# quadcopter_2.net
KiCad netlist of a schematic drawn in EAGLE
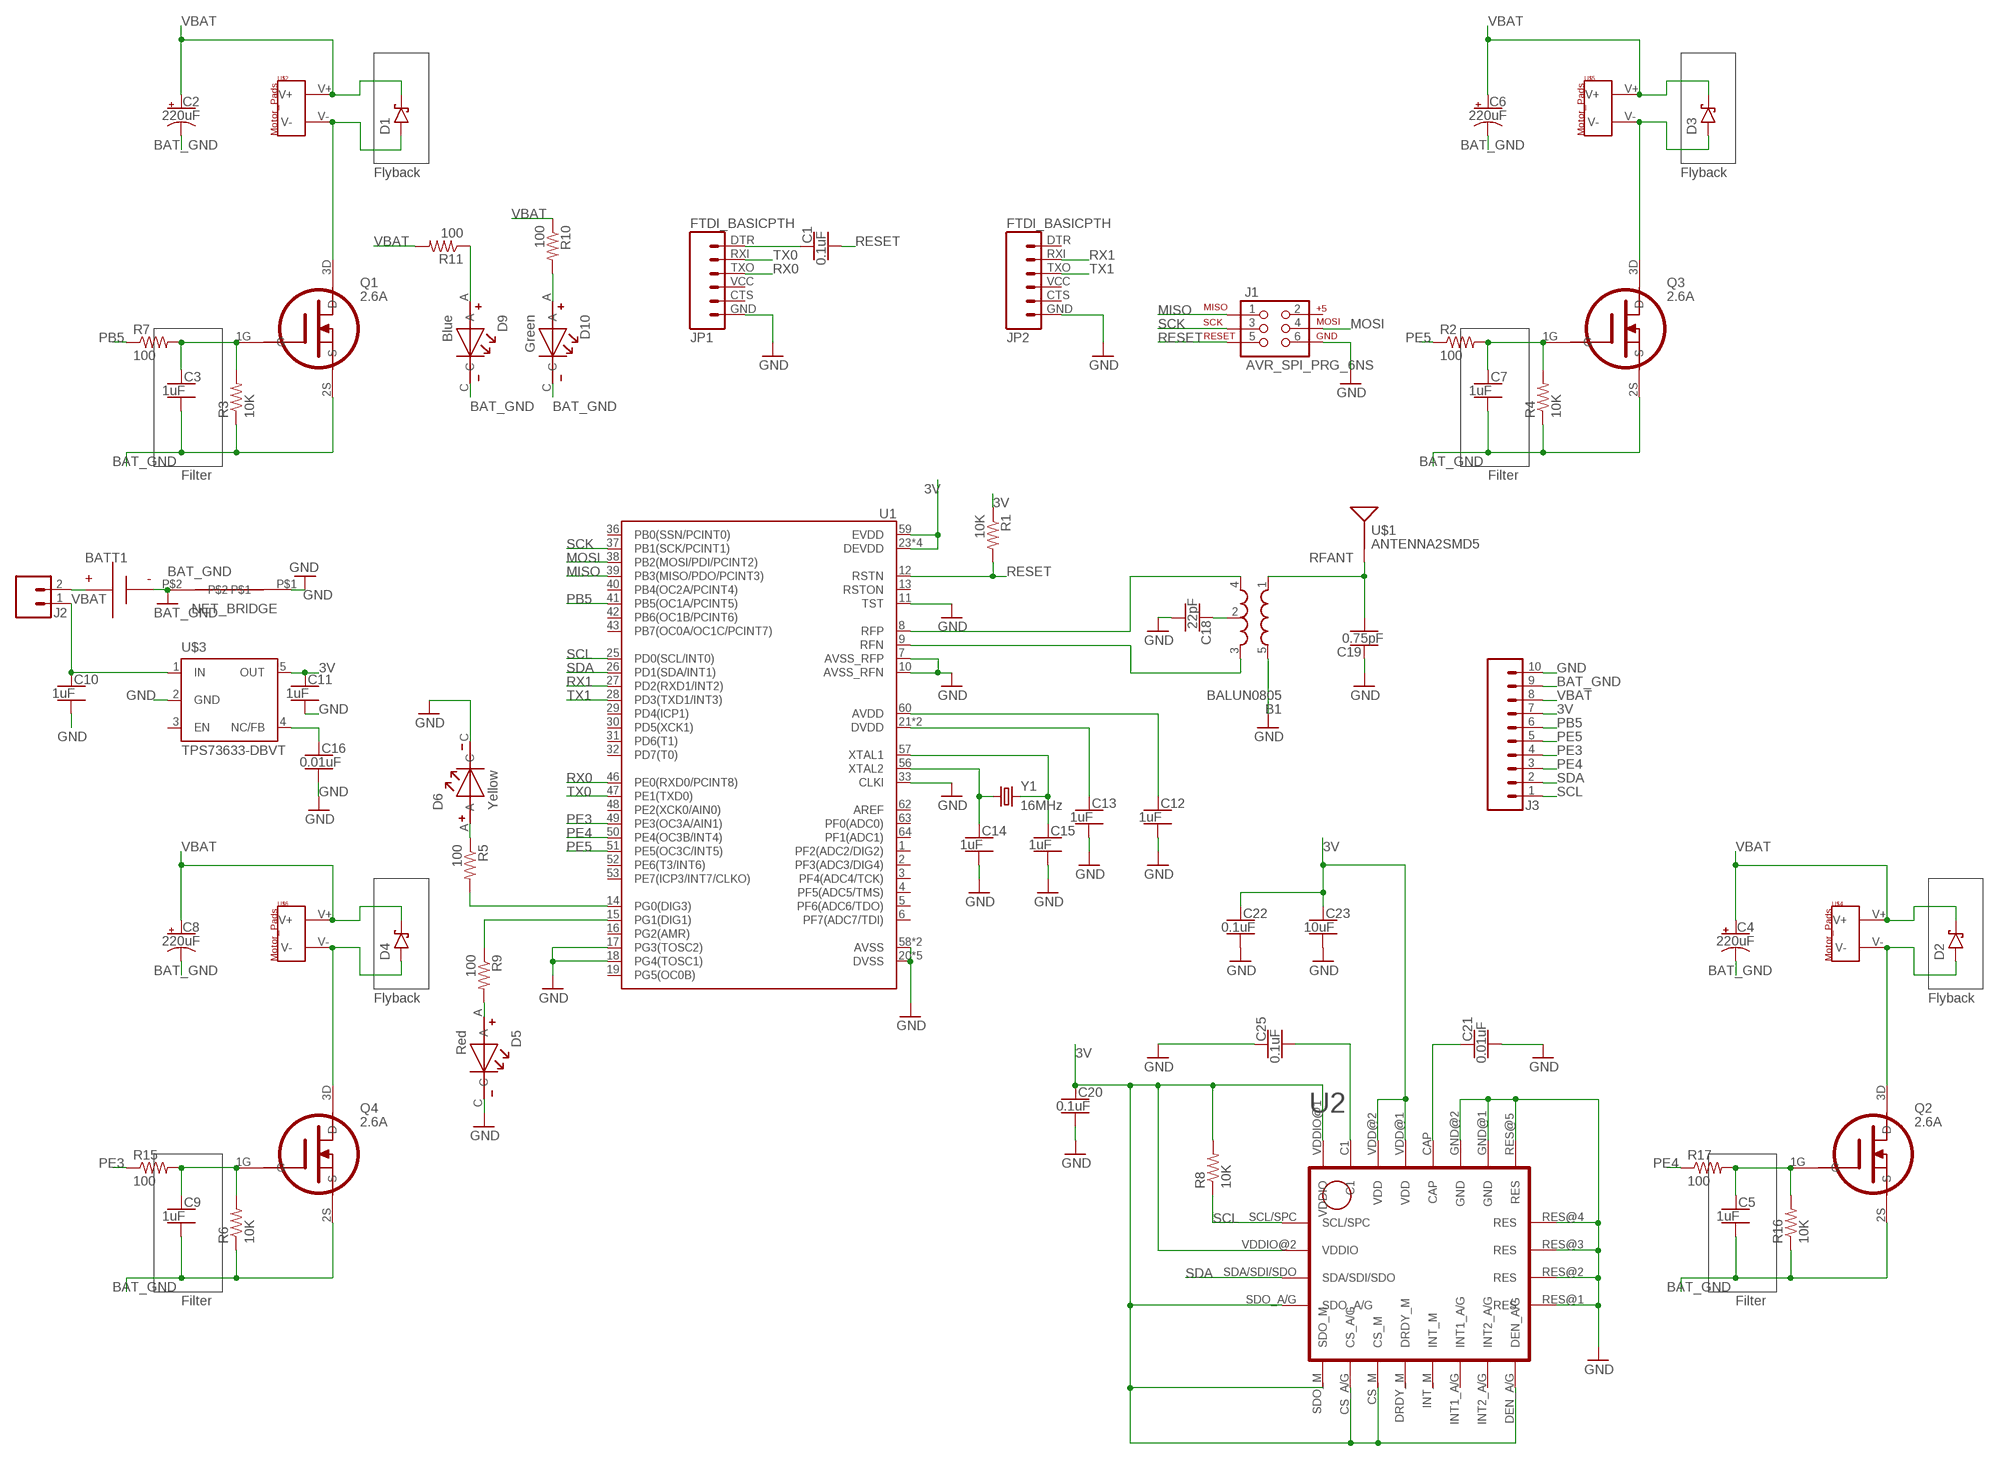
[diagram p0: schematic, sheet 1]

(export (version "E")
  (design (tool "Eeschema 10.0.6"))
  (components
    (comp (ref "B1")
      (value "BALUN0805")
      (footprint "eagle-import:BALUN")
      (fields (field (name "MFR") "Wurth Electronics Inc") (field (name "MPN") "748421245"))
      (libsource (lib "eagle-import") (part "BALUN0805"))
    )
    (comp (ref "BATT1")
      (value "BATTERY-HUBSAN-W/HOLDER")
      (footprint "eagle-import:BATTERY-W_HOLDER-380MAH-HUBSAN")
      (fields
        (field (name "MFR") "HUBSAN")
        (field (name "MPN") "X4-H107C-8-in-1")
        (field (name "CREATOR") "Swanson")
      )
      (libsource (lib "eagle-import") (part "BATTERY-HUBSAN-W/HOLDER"))
    )
    (comp (ref "C1")
      (value "0.1uF")
      (footprint "eagle-import:CERAMIC_CAP_0805")
      (fields
        (field (name "MFR") "Murata Electronics North America")
        (field (name "MPN") "GRM21BR71H104KA01L")
        (field (name "CREATOR") "SWANSON")
      )
      (libsource (lib "eagle-import") (part "CERAMIC_CAP-0805-0.1UF"))
    )
    (comp (ref "C2")
      (value "220uF")
      (footprint "eagle-import:CAPMP7343X310_HS")
      (fields (field (name "MFR") "AVX Corporation") (field (name "MPN") "TAJD227K006RNJ"))
      (libsource (lib "eagle-import") (part "CAPACITOR-POL_SMD-7043-D_TANTALUM-220UF"))
    )
    (comp (ref "C3")
      (value "1uF")
      (footprint "eagle-import:CAPC2012X140_HS")
      (fields
        (field (name "MFR") "Murata Electronics North America")
        (field (name "MPN") "GRM21BR71H105KA12L")
      )
      (libsource (lib "eagle-import") (part "CAPACITOR-NP_SMD-2012-0805_CERAMIC-1UF"))
    )
    (comp (ref "C4")
      (value "220uF")
      (footprint "eagle-import:CAPMP7343X310_HS")
      (fields (field (name "MFR") "AVX Corporation") (field (name "MPN") "TAJD227K006RNJ"))
      (libsource (lib "eagle-import") (part "CAPACITOR-POL_SMD-7043-D_TANTALUM-220UF"))
    )
    (comp (ref "C5")
      (value "1uF")
      (footprint "eagle-import:CAPC2012X140_HS")
      (fields
        (field (name "MFR") "Murata Electronics North America")
        (field (name "MPN") "GRM21BR71H105KA12L")
      )
      (libsource (lib "eagle-import") (part "CAPACITOR-NP_SMD-2012-0805_CERAMIC-1UF"))
    )
    (comp (ref "C6")
      (value "220uF")
      (footprint "eagle-import:CAPMP7343X310_HS")
      (fields (field (name "MFR") "AVX Corporation") (field (name "MPN") "TAJD227K006RNJ"))
      (libsource (lib "eagle-import") (part "CAPACITOR-POL_SMD-7043-D_TANTALUM-220UF"))
    )
    (comp (ref "C7")
      (value "1uF")
      (footprint "eagle-import:CAPC2012X140_HS")
      (fields
        (field (name "MFR") "Murata Electronics North America")
        (field (name "MPN") "GRM21BR71H105KA12L")
      )
      (libsource (lib "eagle-import") (part "CAPACITOR-NP_SMD-2012-0805_CERAMIC-1UF"))
    )
    (comp (ref "C8")
      (value "220uF")
      (footprint "eagle-import:CAPMP7343X310_HS")
      (fields (field (name "MFR") "AVX Corporation") (field (name "MPN") "TAJD227K006RNJ"))
      (libsource (lib "eagle-import") (part "CAPACITOR-POL_SMD-7043-D_TANTALUM-220UF"))
    )
    (comp (ref "C9")
      (value "1uF")
      (footprint "eagle-import:CAPC2012X140_HS")
      (fields
        (field (name "MFR") "Murata Electronics North America")
        (field (name "MPN") "GRM21BR71H105KA12L")
      )
      (libsource (lib "eagle-import") (part "CAPACITOR-NP_SMD-2012-0805_CERAMIC-1UF"))
    )
    (comp (ref "C10")
      (value "1uF")
      (footprint "eagle-import:CAPC2012X140_HS")
      (fields
        (field (name "MFR") "Murata Electronics North America")
        (field (name "MPN") "GRM21BR71H105KA12L")
      )
      (libsource (lib "eagle-import") (part "CAPACITOR-NP_SMD-2012-0805_CERAMIC-1UF"))
    )
    (comp (ref "C11")
      (value "1uF")
      (footprint "eagle-import:CAPC2012X140_HS")
      (fields
        (field (name "MFR") "Murata Electronics North America")
        (field (name "MPN") "GRM21BR71H105KA12L")
      )
      (libsource (lib "eagle-import") (part "CAPACITOR-NP_SMD-2012-0805_CERAMIC-1UF"))
    )
    (comp (ref "C12")
      (value "1uF")
      (footprint "eagle-import:CAPC2012X140_HS")
      (fields
        (field (name "MFR") "Murata Electronics North America")
        (field (name "MPN") "GRM21BR71H105KA12L")
      )
      (libsource (lib "eagle-import") (part "CAPACITOR-NP_SMD-2012-0805_CERAMIC-1UF"))
    )
    (comp (ref "C13")
      (value "1uF")
      (footprint "eagle-import:CAPC2012X140_HS")
      (fields
        (field (name "MFR") "Murata Electronics North America")
        (field (name "MPN") "GRM21BR71H105KA12L")
      )
      (libsource (lib "eagle-import") (part "CAPACITOR-NP_SMD-2012-0805_CERAMIC-1UF"))
    )
    (comp (ref "C14")
      (value "1uF")
      (footprint "eagle-import:CAPC2012X140_HS")
      (fields
        (field (name "MFR") "Murata Electronics North America")
        (field (name "MPN") "GRM21BR71H105KA12L")
      )
      (libsource (lib "eagle-import") (part "CAPACITOR-NP_SMD-2012-0805_CERAMIC-1UF"))
    )
    (comp (ref "C15")
      (value "1uF")
      (footprint "eagle-import:CAPC2012X140_HS")
      (fields
        (field (name "MFR") "Murata Electronics North America")
        (field (name "MPN") "GRM21BR71H105KA12L")
      )
      (libsource (lib "eagle-import") (part "CAPACITOR-NP_SMD-2012-0805_CERAMIC-1UF"))
    )
    (comp (ref "C16")
      (value "0.01uF")
      (footprint "eagle-import:CAPC2012X140_HS")
      (fields
        (field (name "MFR") "Murata Electronics North America")
        (field (name "MPN") "GRM2195C1H103FA01D")
      )
      (libsource (lib "eagle-import") (part "CAPACITOR-NP_SMD-2012-0805_CERAMIC-0.01UF"))
    )
    (comp (ref "C18")
      (value "22pF")
      (footprint "eagle-import:CAPC2012X140_HS")
      (fields
        (field (name "MFR") "Murata Electronics North America")
        (field (name "MPN") "GRM21A5C2E220JW01D")
      )
      (libsource (lib "eagle-import") (part "CAPACITOR-NP_SMD-2012-0805_CERAMIC-22PF"))
    )
    (comp (ref "C19")
      (value "0.75pF")
      (footprint "eagle-import:CAPC2012X140_HS")
      (fields
        (field (name "MFR") "Murata Electronics North America")
        (field (name "MPN") "GQM2195C2AR75CB01D")
      )
      (libsource (lib "eagle-import") (part "CAPACITOR-NP_SMD-2012-0805_CERAMIC-0.75PF"))
    )
    (comp (ref "C20")
      (value "0.1uF")
      (footprint "eagle-import:CAPC2012X140_HS")
      (fields
        (field (name "MFR") "Murata Electronics North America")
        (field (name "MPN") "GRM21BR71H104KA01L")
      )
      (libsource (lib "eagle-import") (part "CAPACITOR-NP_SMD-2012-0805_CERAMIC-0.1UF"))
    )
    (comp (ref "C21")
      (value "0.01uF")
      (footprint "eagle-import:CAPC2012X140_HS")
      (fields
        (field (name "MFR") "Murata Electronics North America")
        (field (name "MPN") "GRM2195C1H103FA01D")
      )
      (libsource (lib "eagle-import") (part "CAPACITOR-NP_SMD-2012-0805_CERAMIC-0.01UF"))
    )
    (comp (ref "C22")
      (value "0.1uF")
      (footprint "eagle-import:CAPC2012X140_HS")
      (fields
        (field (name "MFR") "Murata Electronics North America")
        (field (name "MPN") "GRM21BR71H104KA01L")
      )
      (libsource (lib "eagle-import") (part "CAPACITOR-NP_SMD-2012-0805_CERAMIC-0.1UF"))
    )
    (comp (ref "C23")
      (value "10uF")
      (footprint "eagle-import:CAPC2012X140_HS")
      (fields
        (field (name "MFR") "Murata Electronics North America")
        (field (name "MPN") "GRM21BR61E106KA73L")
      )
      (libsource (lib "eagle-import") (part "CAPACITOR-NP_SMD-2012-0805_CERAMIC-10UF"))
    )
    (comp (ref "C25")
      (value "0.1uF")
      (footprint "eagle-import:CAPC2012X140_HS")
      (fields
        (field (name "MFR") "Murata Electronics North America")
        (field (name "MPN") "GRM21BR71H104KA01L")
      )
      (libsource (lib "eagle-import") (part "CAPACITOR-NP_SMD-2012-0805_CERAMIC-0.1UF"))
    )
    (comp (ref "D1")
      (value "DIODE-SCHOTTKY_SMD-SOD123")
      (footprint "eagle-import:SOD3716X135_HS")
      (libsource (lib "eagle-import") (part "DIODE-SCHOTTKY_SMD-SOD123"))
    )
    (comp (ref "D2")
      (value "DIODE-SCHOTTKY_SMD-SOD123")
      (footprint "eagle-import:SOD3716X135_HS")
      (libsource (lib "eagle-import") (part "DIODE-SCHOTTKY_SMD-SOD123"))
    )
    (comp (ref "D3")
      (value "DIODE-SCHOTTKY_SMD-SOD123")
      (footprint "eagle-import:SOD3716X135_HS")
      (libsource (lib "eagle-import") (part "DIODE-SCHOTTKY_SMD-SOD123"))
    )
    (comp (ref "D4")
      (value "DIODE-SCHOTTKY_SMD-SOD123")
      (footprint "eagle-import:SOD3716X135_HS")
      (libsource (lib "eagle-import") (part "DIODE-SCHOTTKY_SMD-SOD123"))
    )
    (comp (ref "D5")
      (value "Red")
      (footprint "eagle-import:LED_VLMX51Z1AA")
      (fields
        (field (name "MFR") "Vishay")
        (field (name "MPN") "VLMR51Z1AA-GS08")
        (field (name "CREATOR") "Jason Shiuan")
      )
      (libsource (lib "eagle-import") (part "LED_VLMX51Z1AARED"))
    )
    (comp (ref "D6")
      (value "Yellow")
      (footprint "eagle-import:LED_VLMX51Z1AA")
      (fields
        (field (name "MFR") "Vishay")
        (field (name "MPN") "VLMY51Z1AA-GS08")
        (field (name "CREATOR") "Jason Shiuan")
      )
      (libsource (lib "eagle-import") (part "LED_VLMX51Z1AAYELLOW"))
    )
    (comp (ref "D9")
      (value "Blue")
      (footprint "eagle-import:LED_OVS5MXBCR4")
      (fields
        (field (name "MFR") "TT Electronics/Optek Technology")
        (field (name "MPN") "OVS5MBBCR4")
        (field (name "CREATOR") "Jason Shiuan")
      )
      (libsource (lib "eagle-import") (part "LED_OVS5MXBCR4BLUE"))
    )
    (comp (ref "D10")
      (value "Green")
      (footprint "eagle-import:LED_OVS5MXBCR4")
      (fields
        (field (name "MFR") "TT Electronics/Optek Technology")
        (field (name "MPN") "OVS5MGBCR4")
        (field (name "CREATOR") "Jason Shiuan")
      )
      (libsource (lib "eagle-import") (part "LED_OVS5MXBCR4GREEN"))
    )
    (comp (ref "J1")
      (value "AVR_SPI_PRG_6NS")
      (footprint "eagle-import:2X3-NS")
      (fields (field (name "MFR") "Amphenol FCI") (field (name "MPN") "67997-206HLF"))
      (libsource (lib "eagle-import") (part "AVR_SPI_PRG_6NS"))
    )
    (comp (ref "J2")
      (value "MALE_HEADER_2POS-2X1-0.1IN")
      (footprint "eagle-import:MALE_HEADER_2X1_0.1IN")
      (fields
        (field (name "MFR") "3M")
        (field (name "MPN") "961102-6404-AR")
        (field (name "CREATOR") "SWANSON")
      )
      (libsource (lib "eagle-import") (part "MALE_HEADER_2POS-2X1-0.1IN"))
    )
    (comp (ref "J3")
      (value "SIP-10_TH-254X10")
      (footprint "eagle-import:HDRV10W63P254_10X1_2540X254H838_HS")
      (fields (field (name "MFR") "Amphenol FCI") (field (name "MPN") "68000-110HLF"))
      (libsource (lib "eagle-import") (part "SIP-10_TH-254X10"))
    )
    (comp (ref "JP1")
      (value "FTDI_BASICPTH")
      (footprint "eagle-import:FTDI_BASIC")
      (fields (field (name "MFR") "Amphenol FCI") (field (name "MPN") "68016-406HLF"))
      (libsource (lib "eagle-import") (part "FTDI_BASICPTH"))
    )
    (comp (ref "JP2")
      (value "FTDI_BASICPTH")
      (footprint "eagle-import:FTDI_BASIC")
      (fields (field (name "MFR") "Amphenol FCI") (field (name "MPN") "68016-406HLF"))
      (libsource (lib "eagle-import") (part "FTDI_BASICPTH"))
    )
    (comp (ref "NET_BRIDGE")
      (value "NET_BRIDGE")
      (footprint "eagle-import:NET_BRIDGE")
      (fields (field (name "CREATPR") "Jason Shiuan"))
      (libsource (lib "eagle-import") (part "NET_BRIDGE"))
    )
    (comp (ref "Q1")
      (value "2.6A")
      (footprint "eagle-import:N_MOSFET_SI2302CDS_T1_E3")
      (fields
        (field (name "MFR") "Vishay Siliconix")
        (field (name "MPN") "SI2302CDS-T1-E3")
        (field (name "CREATOR") "Connie Du")
      )
      (libsource (lib "eagle-import") (part "N_MOSFET_SI2302CDS_T1_E3"))
    )
    (comp (ref "Q2")
      (value "2.6A")
      (footprint "eagle-import:N_MOSFET_SI2302CDS_T1_E3")
      (fields
        (field (name "MFR") "Vishay Siliconix")
        (field (name "MPN") "SI2302CDS-T1-E3")
        (field (name "CREATOR") "Connie Du")
      )
      (libsource (lib "eagle-import") (part "N_MOSFET_SI2302CDS_T1_E3"))
    )
    (comp (ref "Q3")
      (value "2.6A")
      (footprint "eagle-import:N_MOSFET_SI2302CDS_T1_E3")
      (fields
        (field (name "MFR") "Vishay Siliconix")
        (field (name "MPN") "SI2302CDS-T1-E3")
        (field (name "CREATOR") "Connie Du")
      )
      (libsource (lib "eagle-import") (part "N_MOSFET_SI2302CDS_T1_E3"))
    )
    (comp (ref "Q4")
      (value "2.6A")
      (footprint "eagle-import:N_MOSFET_SI2302CDS_T1_E3")
      (fields
        (field (name "MFR") "Vishay Siliconix")
        (field (name "MPN") "SI2302CDS-T1-E3")
        (field (name "CREATOR") "Connie Du")
      )
      (libsource (lib "eagle-import") (part "N_MOSFET_SI2302CDS_T1_E3"))
    )
    (comp (ref "R1")
      (value "10K")
      (footprint "eagle-import:RESC2012X60_HS")
      (fields (field (name "MFR") "Yageo") (field (name "MPN") "RC0805JR-0710KL"))
      (libsource (lib "eagle-import") (part "RESISTOR_SMD-2012-0805-10K"))
    )
    (comp (ref "R2")
      (value "100")
      (footprint "eagle-import:RESC2012X60_HS")
      (fields (field (name "MFR") "Yageo") (field (name "MPN") "RC0805JR-07100RL"))
      (libsource (lib "eagle-import") (part "RESISTOR_SMD-2012-0805-100"))
    )
    (comp (ref "R3")
      (value "10K")
      (footprint "eagle-import:RESC2012X60_HS")
      (fields (field (name "MFR") "Yageo") (field (name "MPN") "RC0805JR-0710KL"))
      (libsource (lib "eagle-import") (part "RESISTOR_SMD-2012-0805-10K"))
    )
    (comp (ref "R4")
      (value "10K")
      (footprint "eagle-import:RESC2012X60_HS")
      (fields (field (name "MFR") "Yageo") (field (name "MPN") "RC0805JR-0710KL"))
      (libsource (lib "eagle-import") (part "RESISTOR_SMD-2012-0805-10K"))
    )
    (comp (ref "R5")
      (value "100")
      (footprint "eagle-import:RESC2012X60_HS")
      (fields (field (name "MFR") "Yageo") (field (name "MPN") "RC0805JR-07100RL"))
      (libsource (lib "eagle-import") (part "RESISTOR_SMD-2012-0805-100"))
    )
    (comp (ref "R6")
      (value "10K")
      (footprint "eagle-import:RESC2012X60_HS")
      (fields (field (name "MFR") "Yageo") (field (name "MPN") "RC0805JR-0710KL"))
      (libsource (lib "eagle-import") (part "RESISTOR_SMD-2012-0805-10K"))
    )
    (comp (ref "R7")
      (value "100")
      (footprint "eagle-import:RESC2012X60_HS")
      (fields (field (name "MFR") "Yageo") (field (name "MPN") "RC0805JR-07100RL"))
      (libsource (lib "eagle-import") (part "RESISTOR_SMD-2012-0805-100"))
    )
    (comp (ref "R8")
      (value "10K")
      (footprint "eagle-import:RESC2012X60_HS")
      (fields (field (name "MFR") "Yageo") (field (name "MPN") "RC0805JR-0710KL"))
      (libsource (lib "eagle-import") (part "RESISTOR_SMD-2012-0805-10K"))
    )
    (comp (ref "R9")
      (value "100")
      (footprint "eagle-import:RESC2012X60_HS")
      (fields (field (name "MFR") "Yageo") (field (name "MPN") "RC0805JR-07100RL"))
      (libsource (lib "eagle-import") (part "RESISTOR_SMD-2012-0805-100"))
    )
    (comp (ref "R10")
      (value "100")
      (footprint "eagle-import:RESC2012X60_HS")
      (fields (field (name "MFR") "Yageo") (field (name "MPN") "RC0805JR-07100RL"))
      (libsource (lib "eagle-import") (part "RESISTOR_SMD-2012-0805-100"))
    )
    (comp (ref "R11")
      (value "100")
      (footprint "eagle-import:RESC2012X60_HS")
      (fields (field (name "MFR") "Yageo") (field (name "MPN") "RC0805JR-07100RL"))
      (libsource (lib "eagle-import") (part "RESISTOR_SMD-2012-0805-100"))
    )
    (comp (ref "R15")
      (value "100")
      (footprint "eagle-import:RESC2012X60_HS")
      (fields (field (name "MFR") "Yageo") (field (name "MPN") "RC0805JR-07100RL"))
      (libsource (lib "eagle-import") (part "RESISTOR_SMD-2012-0805-100"))
    )
    (comp (ref "R16")
      (value "10K")
      (footprint "eagle-import:RESC2012X60_HS")
      (fields (field (name "MFR") "Yageo") (field (name "MPN") "RC0805JR-0710KL"))
      (libsource (lib "eagle-import") (part "RESISTOR_SMD-2012-0805-10K"))
    )
    (comp (ref "R17")
      (value "100")
      (footprint "eagle-import:RESC2012X60_HS")
      (fields (field (name "MFR") "Yageo") (field (name "MPN") "RC0805JR-07100RL"))
      (libsource (lib "eagle-import") (part "RESISTOR_SMD-2012-0805-100"))
    )
    (comp (ref "U$1")
      (value "ANTENNA2SMD5")
      (footprint "eagle-import:ANTENNA-CHIP5")
      (fields (field (name "MFR") "Linx Technologies Inc.") (field (name "MPN") "ANT-2.45-CHP-T"))
      (libsource (lib "eagle-import") (part "ANTENNA2SMD5"))
    )
    (comp (ref "U$2")
      (value "MOTOR_PADS")
      (footprint "eagle-import:MOTOR_PADS")
      (fields (field (name "MFR") "NA"))
      (libsource (lib "eagle-import") (part "MOTOR_PADS"))
    )
    (comp (ref "U$3")
      (value "TPS73633-DBVT")
      (footprint "eagle-import:SOT23-DBV")
      (fields (field (name "MFR") "Texas Instruments") (field (name "MPN") "LP3985IM5X-3.0/NOPB"))
      (libsource (lib "eagle-import") (part "TPS73633-DBVT"))
    )
    (comp (ref "U$4")
      (value "MOTOR_PADS")
      (footprint "eagle-import:MOTOR_PADS")
      (fields (field (name "MFR") "NA"))
      (libsource (lib "eagle-import") (part "MOTOR_PADS"))
    )
    (comp (ref "U$5")
      (value "MOTOR_PADS")
      (footprint "eagle-import:MOTOR_PADS")
      (fields (field (name "MFR") "NA"))
      (libsource (lib "eagle-import") (part "MOTOR_PADS"))
    )
    (comp (ref "U$6")
      (value "MOTOR_PADS")
      (footprint "eagle-import:MOTOR_PADS")
      (fields (field (name "MFR") "NA"))
      (libsource (lib "eagle-import") (part "MOTOR_PADS"))
    )
    (comp (ref "U1")
      (value "ATMEGA128RFA1")
      (footprint "eagle-import:QFN-64")
      (fields
        (field (name "MFR") "Atmel")
        (field (name "MPN") "ATMEGA128RFA1-ZUR00")
        (field (name "CREATOR") "Swanson")
      )
      (libsource (lib "eagle-import") (part "ATMEGA128RFA1"))
    )
    (comp (ref "U2")
      (value "IMU_LSM9DS1TR")
      (footprint "eagle-import:IMU_LSM9DS1TR")
      (fields
        (field (name "MFR") "STMicroelectronics")
        (field (name "MPN") "LSM9DS1TR")
        (field (name "CREATOR") "Connie Du")
      )
      (libsource (lib "eagle-import") (part "IMU_LSM9DS1TR"))
    )
    (comp (ref "Y1")
      (value "16MHz")
      (footprint "eagle-import:CRYSTAL-SMD-5X3")
      (fields (field (name "MFR") "Abracon LLC") (field (name "MPN") "ABM3B-16.000MHZ-B2-T"))
      (libsource (lib "eagle-import") (part "CRYSTAL5X3"))
    )
  )
  (nets
    (net (code "1") (name "/3V") (class "Default")
      (node (ref "C11") (pin "1") (pinfunction "1_1") (pintype "passive"))
      (node (ref "C20") (pin "1") (pinfunction "1_1") (pintype "passive"))
      (node (ref "C22") (pin "1") (pinfunction "1_1") (pintype "passive"))
      (node (ref "C23") (pin "1") (pinfunction "1_1") (pintype "passive"))
      (node (ref "J3") (pin "7") (pinfunction "7_7") (pintype "passive"))
      (node (ref "R1") (pin "1") (pinfunction "1_1") (pintype "passive"))
      (node (ref "R8") (pin "2") (pinfunction "2_2") (pintype "passive"))
      (node (ref "U$3") (pin "5") (pinfunction "OUT_5") (pintype "passive"))
      (node (ref "U1") (pin "23") (pinfunction "DEVDD_23") (pintype "bidirectional"))
      (node (ref "U1") (pin "34") (pinfunction "DEVDD_34") (pintype "bidirectional"))
      (node (ref "U1") (pin "44") (pinfunction "DEVDD_44") (pintype "bidirectional"))
      (node (ref "U1") (pin "54") (pinfunction "DEVDD_54") (pintype "bidirectional"))
      (node (ref "U1") (pin "59") (pinfunction "EVDD_59") (pintype "bidirectional"))
      (node (ref "U2") (pin "CS_A/G") (pinfunction "CS_A/G_CS_A/G") (pintype "bidirectional"))
      (node (ref "U2") (pin "CS_M") (pinfunction "CS_M_CS_M") (pintype "bidirectional"))
      (node (ref "U2") (pin "DEN_A/G") (pinfunction "DEN_A/G_DEN_A/G") (pintype "bidirectional"))
      (node (ref "U2") (pin "SDO_A/G") (pinfunction "SDO_A/G_SDO_A/G") (pintype "bidirectional"))
      (node (ref "U2") (pin "SDO_M") (pinfunction "SDO_M_SDO_M") (pintype "bidirectional"))
      (node (ref "U2") (pin "VDD@1") (pinfunction "VDD_VDD@1") (pintype "bidirectional"))
      (node (ref "U2") (pin "VDD@2") (pinfunction "VDD_VDD@2") (pintype "bidirectional"))
      (node (ref "U2") (pin "VDDIO@1") (pinfunction "VDDIO_VDDIO@1") (pintype "bidirectional"))
      (node (ref "U2") (pin "VDDIO@2") (pinfunction "VDDIO_VDDIO@2") (pintype "bidirectional"))
    )
    (net (code "2") (name "/MISO") (class "Default")
      (node (ref "U1") (pin "39") (pinfunction "PB3(MISO/PDO/PCINT3)_39") (pintype "bidirectional"))
    )
    (net (code "3") (name "/MOSI") (class "Default")
      (node (ref "U1") (pin "38") (pinfunction "PB2(MOSI/PDI/PCINT2)_38") (pintype "bidirectional"))
    )
    (net (code "4") (name "/PB5") (class "Default")
      (node (ref "J3") (pin "6") (pinfunction "6_6") (pintype "passive"))
      (node (ref "R7") (pin "1") (pinfunction "1_1") (pintype "passive"))
      (node (ref "U1") (pin "41") (pinfunction "PB5(OC1A/PCINT5)_41") (pintype "bidirectional"))
    )
    (net (code "5") (name "/PE3") (class "Default")
      (node (ref "J3") (pin "4") (pinfunction "4_4") (pintype "passive"))
      (node (ref "R15") (pin "1") (pinfunction "1_1") (pintype "passive"))
      (node (ref "U1") (pin "49") (pinfunction "PE3(OC3A/AIN1)_49") (pintype "bidirectional"))
    )
    (net (code "6") (name "/PE4") (class "Default")
      (node (ref "J3") (pin "3") (pinfunction "3_3") (pintype "passive"))
      (node (ref "R17") (pin "1") (pinfunction "1_1") (pintype "passive"))
      (node (ref "U1") (pin "50") (pinfunction "PE4(OC3B/INT4)_50") (pintype "bidirectional"))
    )
    (net (code "7") (name "/PE5") (class "Default")
      (node (ref "J3") (pin "5") (pinfunction "5_5") (pintype "passive"))
      (node (ref "R2") (pin "1") (pinfunction "1_1") (pintype "passive"))
      (node (ref "U1") (pin "51") (pinfunction "PE5(OC3C/INT5)_51") (pintype "bidirectional"))
    )
    (net (code "8") (name "/RESET") (class "Default")
      (node (ref "R1") (pin "2") (pinfunction "2_2") (pintype "passive"))
      (node (ref "U1") (pin "12") (pinfunction "RSTN_12") (pintype "bidirectional"))
    )
    (net (code "9") (name "/RFANT") (class "Default")
      (node (ref "B1") (pin "1") (pinfunction "IN_1") (pintype "bidirectional"))
      (node (ref "C19") (pin "2") (pinfunction "2_2") (pintype "passive"))
      (node (ref "U$1") (pin "FEED") (pinfunction "SIGNAL_FEED") (pintype "bidirectional"))
    )
    (net (code "10") (name "/RX0") (class "Default")
      (node (ref "U1") (pin "46") (pinfunction "PE0(RXD0/PCINT8)_46") (pintype "bidirectional"))
    )
    (net (code "11") (name "/RX1") (class "Default")
      (node (ref "U1") (pin "27") (pinfunction "PD2(RXD1/INT2)_27") (pintype "bidirectional"))
    )
    (net (code "12") (name "/SCK") (class "Default")
      (node (ref "U1") (pin "37") (pinfunction "PB1(SCK/PCINT1)_37") (pintype "bidirectional"))
    )
    (net (code "13") (name "/SCL") (class "Default")
      (node (ref "J3") (pin "1") (pinfunction "1_1") (pintype "passive"))
      (node (ref "R8") (pin "1") (pinfunction "1_1") (pintype "passive"))
      (node (ref "U1") (pin "25") (pinfunction "PD0(SCL/INT0)_25") (pintype "bidirectional"))
      (node (ref "U2") (pin "SCL/SPC") (pinfunction "SCL/SPC_SCL/SPC") (pintype "bidirectional"))
    )
    (net (code "14") (name "/SDA") (class "Default")
      (node (ref "J3") (pin "2") (pinfunction "2_2") (pintype "passive"))
      (node (ref "U1") (pin "26") (pinfunction "PD1(SDA/INT1)_26") (pintype "bidirectional"))
      (node (ref "U2") (pin "SDA/SDI/SDO") (pinfunction "SDA/SDI/SDO_SDA/SDI/SDO") (pintype "bidirectional"))
    )
    (net (code "15") (name "/TX0") (class "Default")
      (node (ref "U1") (pin "47") (pinfunction "PE1(TXD0)_47") (pintype "bidirectional"))
    )
    (net (code "16") (name "/TX1") (class "Default")
      (node (ref "U1") (pin "28") (pinfunction "PD3(TXD1/INT3)_28") (pintype "bidirectional"))
    )
    (net (code "17") (name "/VBAT") (class "Default")
      (node (ref "C10") (pin "1") (pinfunction "1_1") (pintype "passive"))
      (node (ref "C2") (pin "1") (pinfunction "+_1") (pintype "passive"))
      (node (ref "C4") (pin "1") (pinfunction "+_1") (pintype "passive"))
      (node (ref "C6") (pin "1") (pinfunction "+_1") (pintype "passive"))
      (node (ref "C8") (pin "1") (pinfunction "+_1") (pintype "passive"))
      (node (ref "D1") (pin "C") (pinfunction "C_C") (pintype "passive"))
      (node (ref "D2") (pin "C") (pinfunction "C_C") (pintype "passive"))
      (node (ref "D3") (pin "C") (pinfunction "C_C") (pintype "passive"))
      (node (ref "D4") (pin "C") (pinfunction "C_C") (pintype "passive"))
      (node (ref "J2") (pin "1") (pinfunction "1_1") (pintype "passive"))
      (node (ref "J3") (pin "8") (pinfunction "8_8") (pintype "passive"))
      (node (ref "R10") (pin "1") (pinfunction "1_1") (pintype "passive"))
      (node (ref "R11") (pin "2") (pinfunction "2_2") (pintype "passive"))
      (node (ref "U$2") (pin "V+") (pinfunction "V+_V+") (pintype "bidirectional"))
      (node (ref "U$3") (pin "1") (pinfunction "IN_1") (pintype "input"))
      (node (ref "U$4") (pin "V+") (pinfunction "V+_V+") (pintype "bidirectional"))
      (node (ref "U$5") (pin "V+") (pinfunction "V+_V+") (pintype "bidirectional"))
      (node (ref "U$6") (pin "V+") (pinfunction "V+_V+") (pintype "bidirectional"))
    )
    (net (code "18") (name "BAT_GND") (class "Default")
      (node (ref "BATT1") (pin "-") (pinfunction "N_-") (pintype "bidirectional"))
      (node (ref "C2") (pin "2") (pinfunction "-_2") (pintype "passive"))
      (node (ref "C3") (pin "2") (pinfunction "2_2") (pintype "passive"))
      (node (ref "C4") (pin "2") (pinfunction "-_2") (pintype "passive"))
      (node (ref "C5") (pin "2") (pinfunction "2_2") (pintype "passive"))
      (node (ref "C6") (pin "2") (pinfunction "-_2") (pintype "passive"))
      (node (ref "C7") (pin "2") (pinfunction "2_2") (pintype "passive"))
      (node (ref "C8") (pin "2") (pinfunction "-_2") (pintype "passive"))
      (node (ref "C9") (pin "2") (pinfunction "2_2") (pintype "passive"))
      (node (ref "D10") (pin "C") (pinfunction "C_C") (pintype "passive"))
      (node (ref "D9") (pin "C") (pinfunction "C_C") (pintype "passive"))
      (node (ref "J3") (pin "9") (pinfunction "9_9") (pintype "passive"))
      (node (ref "NET_BRIDGE") (pin "P$2") (pinfunction "P$2_P$2") (pintype "bidirectional"))
      (node (ref "Q1") (pin "2S") (pinfunction "S_2S") (pintype "bidirectional"))
      (node (ref "Q2") (pin "2S") (pinfunction "S_2S") (pintype "bidirectional"))
      (node (ref "Q3") (pin "2S") (pinfunction "S_2S") (pintype "bidirectional"))
      (node (ref "Q4") (pin "2S") (pinfunction "S_2S") (pintype "bidirectional"))
      (node (ref "R16") (pin "1") (pinfunction "1_1") (pintype "passive"))
      (node (ref "R3") (pin "1") (pinfunction "1_1") (pintype "passive"))
      (node (ref "R4") (pin "1") (pinfunction "1_1") (pintype "passive"))
      (node (ref "R6") (pin "1") (pinfunction "1_1") (pintype "passive"))
    )
    (net (code "19") (name "GND") (class "Default")
      (node (ref "B1") (pin "5") (pinfunction "GND_5") (pintype "bidirectional"))
      (node (ref "C10") (pin "2") (pinfunction "2_2") (pintype "passive"))
      (node (ref "C11") (pin "2") (pinfunction "2_2") (pintype "passive"))
      (node (ref "C12") (pin "2") (pinfunction "2_2") (pintype "passive"))
      (node (ref "C13") (pin "2") (pinfunction "2_2") (pintype "passive"))
      (node (ref "C14") (pin "2") (pinfunction "2_2") (pintype "passive"))
      (node (ref "C15") (pin "2") (pinfunction "2_2") (pintype "passive"))
      (node (ref "C16") (pin "2") (pinfunction "2_2") (pintype "passive"))
      (node (ref "C18") (pin "2") (pinfunction "2_2") (pintype "passive"))
      (node (ref "C19") (pin "1") (pinfunction "1_1") (pintype "passive"))
      (node (ref "C20") (pin "2") (pinfunction "2_2") (pintype "passive"))
      (node (ref "C21") (pin "2") (pinfunction "2_2") (pintype "passive"))
      (node (ref "C22") (pin "2") (pinfunction "2_2") (pintype "passive"))
      (node (ref "C23") (pin "2") (pinfunction "2_2") (pintype "passive"))
      (node (ref "C25") (pin "1") (pinfunction "1_1") (pintype "passive"))
      (node (ref "D5") (pin "C") (pinfunction "C_C") (pintype "passive"))
      (node (ref "D6") (pin "C") (pinfunction "C_C") (pintype "passive"))
      (node (ref "J1") (pin "6") (pinfunction "6_6") (pintype "passive"))
      (node (ref "J3") (pin "10") (pinfunction "10_10") (pintype "passive"))
      (node (ref "JP1") (pin "GND") (pinfunction "6_GND") (pintype "passive"))
      (node (ref "JP2") (pin "GND") (pinfunction "6_GND") (pintype "passive"))
      (node (ref "NET_BRIDGE") (pin "P$1") (pinfunction "P$1_P$1") (pintype "bidirectional"))
      (node (ref "U$3") (pin "2") (pinfunction "GND_2") (pintype "input"))
      (node (ref "U1") (pin "10") (pinfunction "AVSS_RFN_10") (pintype "bidirectional"))
      (node (ref "U1") (pin "11") (pinfunction "TST_11") (pintype "bidirectional"))
      (node (ref "U1") (pin "17") (pinfunction "PG3(TOSC2)_17") (pintype "bidirectional"))
      (node (ref "U1") (pin "18") (pinfunction "PG4(TOSC1)_18") (pintype "bidirectional"))
      (node (ref "U1") (pin "20") (pinfunction "DVSS_20") (pintype "bidirectional"))
      (node (ref "U1") (pin "24") (pinfunction "DVSS_24") (pintype "bidirectional"))
      (node (ref "U1") (pin "33") (pinfunction "CLKI_33") (pintype "bidirectional"))
      (node (ref "U1") (pin "35") (pinfunction "DVSS_35") (pintype "bidirectional"))
      (node (ref "U1") (pin "45") (pinfunction "DVSS_45") (pintype "bidirectional"))
      (node (ref "U1") (pin "55") (pinfunction "DVSS_55") (pintype "bidirectional"))
      (node (ref "U1") (pin "58") (pinfunction "AVSS_58") (pintype "bidirectional"))
      (node (ref "U1") (pin "61") (pinfunction "AVSS_61") (pintype "bidirectional"))
      (node (ref "U1") (pin "7") (pinfunction "AVSS_RFP_7") (pintype "bidirectional"))
      (node (ref "U2") (pin "GND@1") (pinfunction "GND_GND@1") (pintype "bidirectional"))
      (node (ref "U2") (pin "GND@2") (pinfunction "GND_GND@2") (pintype "bidirectional"))
      (node (ref "U2") (pin "RES@1") (pinfunction "RES_RES@1") (pintype "bidirectional"))
      (node (ref "U2") (pin "RES@2") (pinfunction "RES_RES@2") (pintype "bidirectional"))
      (node (ref "U2") (pin "RES@3") (pinfunction "RES_RES@3") (pintype "bidirectional"))
      (node (ref "U2") (pin "RES@4") (pinfunction "RES_RES@4") (pintype "bidirectional"))
      (node (ref "U2") (pin "RES@5") (pinfunction "RES_RES@5") (pintype "bidirectional"))
    )
    (net (code "20") (name "Net-(B1-GND-Pad2)") (class "Default")
      (node (ref "B1") (pin "2") (pinfunction "GND_2") (pintype "bidirectional"))
      (node (ref "C18") (pin "1") (pinfunction "1_1") (pintype "passive"))
    )
    (net (code "21") (name "Net-(B1-OUT1)") (class "Default")
      (node (ref "B1") (pin "4") (pinfunction "OUT1_4") (pintype "bidirectional"))
      (node (ref "U1") (pin "8") (pinfunction "RFP_8") (pintype "bidirectional"))
    )
    (net (code "22") (name "Net-(B1-OUT2)") (class "Default")
      (node (ref "B1") (pin "3") (pinfunction "OUT2_3") (pintype "bidirectional"))
      (node (ref "U1") (pin "9") (pinfunction "RFN_9") (pintype "bidirectional"))
    )
    (net (code "23") (name "Net-(BATT1-P)") (class "Default")
      (node (ref "BATT1") (pin "+") (pinfunction "P_+") (pintype "bidirectional"))
      (node (ref "J2") (pin "2") (pinfunction "2_2") (pintype "passive"))
    )
    (net (code "24") (name "Net-(C13-Pad1)") (class "Default")
      (node (ref "C13") (pin "1") (pinfunction "1_1") (pintype "passive"))
      (node (ref "U1") (pin "21") (pinfunction "DVDD_21") (pintype "bidirectional"))
      (node (ref "U1") (pin "22") (pinfunction "DVDD_22") (pintype "bidirectional"))
    )
    (net (code "25") (name "Net-(C21-Pad1)") (class "Default")
      (node (ref "C21") (pin "1") (pinfunction "1_1") (pintype "passive"))
      (node (ref "U2") (pin "CAP") (pinfunction "CAP_CAP") (pintype "bidirectional"))
    )
    (net (code "26") (name "Net-(C25-Pad2)") (class "Default")
      (node (ref "C25") (pin "2") (pinfunction "2_2") (pintype "passive"))
      (node (ref "U2") (pin "C1") (pinfunction "C1_C1") (pintype "bidirectional"))
    )
    (net (code "27") (name "Net-(D5-PadA)") (class "Default")
      (node (ref "D5") (pin "A") (pinfunction "A_A") (pintype "passive"))
      (node (ref "R9") (pin "2") (pinfunction "2_2") (pintype "passive"))
    )
    (net (code "28") (name "Net-(D6-PadA)") (class "Default")
      (node (ref "D6") (pin "A") (pinfunction "A_A") (pintype "passive"))
      (node (ref "R5") (pin "1") (pinfunction "1_1") (pintype "passive"))
    )
    (net (code "29") (name "Net-(D9-PadA)") (class "Default")
      (node (ref "D9") (pin "A") (pinfunction "A_A") (pintype "passive"))
      (node (ref "R11") (pin "1") (pinfunction "1_1") (pintype "passive"))
    )
    (net (code "30") (name "Net-(D10-PadA)") (class "Default")
      (node (ref "D10") (pin "A") (pinfunction "A_A") (pintype "passive"))
      (node (ref "R10") (pin "2") (pinfunction "2_2") (pintype "passive"))
    )
    (net (code "31") (name "Net-(JP1-1)") (class "Default")
      (node (ref "C1") (pin "1") (pinfunction "1_1") (pintype "passive"))
      (node (ref "JP1") (pin "DTR") (pinfunction "1_DTR") (pintype "passive"))
    )
    (net (code "32") (name "Net-(Q1-D)") (class "Default")
      (node (ref "D1") (pin "A") (pinfunction "A_A") (pintype "passive"))
      (node (ref "Q1") (pin "3D") (pinfunction "D_3D") (pintype "bidirectional"))
      (node (ref "U$2") (pin "V-") (pinfunction "V-_V-") (pintype "bidirectional"))
    )
    (net (code "33") (name "Net-(Q1-G)") (class "Default")
      (node (ref "C3") (pin "1") (pinfunction "1_1") (pintype "passive"))
      (node (ref "Q1") (pin "1G") (pinfunction "G_1G") (pintype "bidirectional"))
      (node (ref "R3") (pin "2") (pinfunction "2_2") (pintype "passive"))
      (node (ref "R7") (pin "2") (pinfunction "2_2") (pintype "passive"))
    )
    (net (code "34") (name "Net-(Q2-D)") (class "Default")
      (node (ref "D2") (pin "A") (pinfunction "A_A") (pintype "passive"))
      (node (ref "Q2") (pin "3D") (pinfunction "D_3D") (pintype "bidirectional"))
      (node (ref "U$4") (pin "V-") (pinfunction "V-_V-") (pintype "bidirectional"))
    )
    (net (code "35") (name "Net-(Q2-G)") (class "Default")
      (node (ref "C5") (pin "1") (pinfunction "1_1") (pintype "passive"))
      (node (ref "Q2") (pin "1G") (pinfunction "G_1G") (pintype "bidirectional"))
      (node (ref "R16") (pin "2") (pinfunction "2_2") (pintype "passive"))
      (node (ref "R17") (pin "2") (pinfunction "2_2") (pintype "passive"))
    )
    (net (code "36") (name "Net-(Q3-D)") (class "Default")
      (node (ref "D3") (pin "A") (pinfunction "A_A") (pintype "passive"))
      (node (ref "Q3") (pin "3D") (pinfunction "D_3D") (pintype "bidirectional"))
      (node (ref "U$5") (pin "V-") (pinfunction "V-_V-") (pintype "bidirectional"))
    )
    (net (code "37") (name "Net-(Q3-G)") (class "Default")
      (node (ref "C7") (pin "1") (pinfunction "1_1") (pintype "passive"))
      (node (ref "Q3") (pin "1G") (pinfunction "G_1G") (pintype "bidirectional"))
      (node (ref "R2") (pin "2") (pinfunction "2_2") (pintype "passive"))
      (node (ref "R4") (pin "2") (pinfunction "2_2") (pintype "passive"))
    )
    (net (code "38") (name "Net-(Q4-D)") (class "Default")
      (node (ref "D4") (pin "A") (pinfunction "A_A") (pintype "passive"))
      (node (ref "Q4") (pin "3D") (pinfunction "D_3D") (pintype "bidirectional"))
      (node (ref "U$6") (pin "V-") (pinfunction "V-_V-") (pintype "bidirectional"))
    )
    (net (code "39") (name "Net-(Q4-G)") (class "Default")
      (node (ref "C9") (pin "1") (pinfunction "1_1") (pintype "passive"))
      (node (ref "Q4") (pin "1G") (pinfunction "G_1G") (pintype "bidirectional"))
      (node (ref "R15") (pin "2") (pinfunction "2_2") (pintype "passive"))
      (node (ref "R6") (pin "2") (pinfunction "2_2") (pintype "passive"))
    )
    (net (code "40") (name "Net-(U$3-NC{slash}FB)") (class "Default")
      (node (ref "C16") (pin "1") (pinfunction "1_1") (pintype "passive"))
      (node (ref "U$3") (pin "4") (pinfunction "NC/FB_4") (pintype "passive"))
    )
    (net (code "41") (name "Net-(U1-AVDD)") (class "Default")
      (node (ref "C12") (pin "1") (pinfunction "1_1") (pintype "passive"))
      (node (ref "U1") (pin "60") (pinfunction "AVDD_60") (pintype "bidirectional"))
    )
    (net (code "42") (name "Net-(U1-PG0(DIG3))") (class "Default")
      (node (ref "R5") (pin "2") (pinfunction "2_2") (pintype "passive"))
      (node (ref "U1") (pin "14") (pinfunction "PG0(DIG3)_14") (pintype "bidirectional"))
    )
    (net (code "43") (name "Net-(U1-PG1(DIG1))") (class "Default")
      (node (ref "R9") (pin "1") (pinfunction "1_1") (pintype "passive"))
      (node (ref "U1") (pin "15") (pinfunction "PG1(DIG1)_15") (pintype "bidirectional"))
    )
    (net (code "44") (name "Net-(U1-XTAL1)") (class "Default")
      (node (ref "C15") (pin "1") (pinfunction "1_1") (pintype "passive"))
      (node (ref "U1") (pin "57") (pinfunction "XTAL1_57") (pintype "bidirectional"))
      (node (ref "Y1") (pin "3") (pinfunction "2_3") (pintype "passive"))
    )
    (net (code "45") (name "Net-(U1-XTAL2)") (class "Default")
      (node (ref "C14") (pin "1") (pinfunction "1_1") (pintype "passive"))
      (node (ref "U1") (pin "56") (pinfunction "XTAL2_56") (pintype "bidirectional"))
      (node (ref "Y1") (pin "1") (pinfunction "1_1") (pintype "passive"))
    )
    (net (code "46") (name "unconnected-(C1-Pad2)") (class "Default")
      (node (ref "C1") (pin "2") (pinfunction "2_2") (pintype "passive"))
    )
    (net (code "47") (name "unconnected-(J1-Pad1)") (class "Default")
      (node (ref "J1") (pin "1") (pinfunction "1_1") (pintype "passive"))
    )
    (net (code "48") (name "unconnected-(J1-Pad2)") (class "Default")
      (node (ref "J1") (pin "2") (pinfunction "2_2") (pintype "passive"))
    )
    (net (code "49") (name "unconnected-(J1-Pad3)") (class "Default")
      (node (ref "J1") (pin "3") (pinfunction "3_3") (pintype "passive"))
    )
    (net (code "50") (name "unconnected-(J1-Pad4)") (class "Default")
      (node (ref "J1") (pin "4") (pinfunction "4_4") (pintype "passive"))
    )
    (net (code "51") (name "unconnected-(J1-Pad5)") (class "Default")
      (node (ref "J1") (pin "5") (pinfunction "5_5") (pintype "passive"))
    )
    (net (code "52") (name "unconnected-(JP1-2-PadRXI)") (class "Default")
      (node (ref "JP1") (pin "RXI") (pinfunction "2_RXI") (pintype "passive"))
    )
    (net (code "53") (name "unconnected-(JP1-3-PadTXO)") (class "Default")
      (node (ref "JP1") (pin "TXO") (pinfunction "3_TXO") (pintype "passive"))
    )
    (net (code "54") (name "unconnected-(JP1-4-PadVCC)") (class "Default")
      (node (ref "JP1") (pin "VCC") (pinfunction "4_VCC") (pintype "passive"))
    )
    (net (code "55") (name "unconnected-(JP1-5-PadCTS)") (class "Default")
      (node (ref "JP1") (pin "CTS") (pinfunction "5_CTS") (pintype "passive"))
    )
    (net (code "56") (name "unconnected-(JP2-1-PadDTR)") (class "Default")
      (node (ref "JP2") (pin "DTR") (pinfunction "1_DTR") (pintype "passive"))
    )
    (net (code "57") (name "unconnected-(JP2-2-PadRXI)") (class "Default")
      (node (ref "JP2") (pin "RXI") (pinfunction "2_RXI") (pintype "passive"))
    )
    (net (code "58") (name "unconnected-(JP2-3-PadTXO)") (class "Default")
      (node (ref "JP2") (pin "TXO") (pinfunction "3_TXO") (pintype "passive"))
    )
    (net (code "59") (name "unconnected-(JP2-4-PadVCC)") (class "Default")
      (node (ref "JP2") (pin "VCC") (pinfunction "4_VCC") (pintype "passive"))
    )
    (net (code "60") (name "unconnected-(JP2-5-PadCTS)") (class "Default")
      (node (ref "JP2") (pin "CTS") (pinfunction "5_CTS") (pintype "passive"))
    )
    (net (code "61") (name "unconnected-(U$3-EN-Pad3)") (class "Default")
      (node (ref "U$3") (pin "3") (pinfunction "EN_3") (pintype "input"))
    )
    (net (code "62") (name "unconnected-(U1-AREF-Pad62)") (class "Default")
      (node (ref "U1") (pin "62") (pinfunction "AREF_62") (pintype "bidirectional"))
    )
    (net (code "63") (name "unconnected-(U1-PB0(SSN{slash}PCINT0)-Pad36)") (class "Default")
      (node (ref "U1") (pin "36") (pinfunction "PB0(SSN/PCINT0)_36") (pintype "bidirectional"))
    )
    (net (code "64") (name "unconnected-(U1-PB4(OC2A{slash}PCINT4)-Pad40)") (class "Default")
      (node (ref "U1") (pin "40") (pinfunction "PB4(OC2A/PCINT4)_40") (pintype "bidirectional"))
    )
    (net (code "65") (name "unconnected-(U1-PB6(OC1B{slash}PCINT6)-Pad42)") (class "Default")
      (node (ref "U1") (pin "42") (pinfunction "PB6(OC1B/PCINT6)_42") (pintype "bidirectional"))
    )
    (net (code "66") (name "unconnected-(U1-PB7(OC0A{slash}OC1C{slash}PCINT7)-Pad43)") (class "Default")
      (node (ref "U1") (pin "43") (pinfunction "PB7(OC0A/OC1C/PCINT7)_43") (pintype "bidirectional"))
    )
    (net (code "67") (name "unconnected-(U1-PD4(ICP1)-Pad29)") (class "Default")
      (node (ref "U1") (pin "29") (pinfunction "PD4(ICP1)_29") (pintype "bidirectional"))
    )
    (net (code "68") (name "unconnected-(U1-PD5(XCK1)-Pad30)") (class "Default")
      (node (ref "U1") (pin "30") (pinfunction "PD5(XCK1)_30") (pintype "bidirectional"))
    )
    (net (code "69") (name "unconnected-(U1-PD6(T1)-Pad31)") (class "Default")
      (node (ref "U1") (pin "31") (pinfunction "PD6(T1)_31") (pintype "bidirectional"))
    )
    (net (code "70") (name "unconnected-(U1-PD7(T0)-Pad32)") (class "Default")
      (node (ref "U1") (pin "32") (pinfunction "PD7(T0)_32") (pintype "bidirectional"))
    )
    (net (code "71") (name "unconnected-(U1-PE2(XCK0{slash}AIN0)-Pad48)") (class "Default")
      (node (ref "U1") (pin "48") (pinfunction "PE2(XCK0/AIN0)_48") (pintype "bidirectional"))
    )
    (net (code "72") (name "unconnected-(U1-PE6(T3{slash}INT6)-Pad52)") (class "Default")
      (node (ref "U1") (pin "52") (pinfunction "PE6(T3/INT6)_52") (pintype "bidirectional"))
    )
    (net (code "73") (name "unconnected-(U1-PE7(ICP3{slash}INT7{slash}CLKO)-Pad53)") (class "Default")
      (node (ref "U1") (pin "53") (pinfunction "PE7(ICP3/INT7/CLKO)_53") (pintype "bidirectional"))
    )
    (net (code "74") (name "unconnected-(U1-PF0(ADC0)-Pad63)") (class "Default")
      (node (ref "U1") (pin "63") (pinfunction "PF0(ADC0)_63") (pintype "bidirectional"))
    )
    (net (code "75") (name "unconnected-(U1-PF1(ADC1)-Pad64)") (class "Default")
      (node (ref "U1") (pin "64") (pinfunction "PF1(ADC1)_64") (pintype "bidirectional"))
    )
    (net (code "76") (name "unconnected-(U1-PF2(ADC2{slash}DIG2)-Pad1)") (class "Default")
      (node (ref "U1") (pin "1") (pinfunction "PF2(ADC2/DIG2)_1") (pintype "bidirectional"))
    )
    (net (code "77") (name "unconnected-(U1-PF3(ADC3{slash}DIG4)-Pad2)") (class "Default")
      (node (ref "U1") (pin "2") (pinfunction "PF3(ADC3/DIG4)_2") (pintype "bidirectional"))
    )
    (net (code "78") (name "unconnected-(U1-PF4(ADC4{slash}TCK)-Pad3)") (class "Default")
      (node (ref "U1") (pin "3") (pinfunction "PF4(ADC4/TCK)_3") (pintype "bidirectional"))
    )
    (net (code "79") (name "unconnected-(U1-PF5(ADC5{slash}TMS)-Pad4)") (class "Default")
      (node (ref "U1") (pin "4") (pinfunction "PF5(ADC5/TMS)_4") (pintype "bidirectional"))
    )
    (net (code "80") (name "unconnected-(U1-PF6(ADC6{slash}TDO)-Pad5)") (class "Default")
      (node (ref "U1") (pin "5") (pinfunction "PF6(ADC6/TDO)_5") (pintype "bidirectional"))
    )
    (net (code "81") (name "unconnected-(U1-PF7(ADC7{slash}TDI)-Pad6)") (class "Default")
      (node (ref "U1") (pin "6") (pinfunction "PF7(ADC7/TDI)_6") (pintype "bidirectional"))
    )
    (net (code "82") (name "unconnected-(U1-PG2(AMR)-Pad16)") (class "Default")
      (node (ref "U1") (pin "16") (pinfunction "PG2(AMR)_16") (pintype "bidirectional"))
    )
    (net (code "83") (name "unconnected-(U1-PG5(OC0B)-Pad19)") (class "Default")
      (node (ref "U1") (pin "19") (pinfunction "PG5(OC0B)_19") (pintype "bidirectional"))
    )
    (net (code "84") (name "unconnected-(U1-RSTON-Pad13)") (class "Default")
      (node (ref "U1") (pin "13") (pinfunction "RSTON_13") (pintype "bidirectional"))
    )
    (net (code "85") (name "unconnected-(U2-PadDRDY_M)") (class "Default")
      (node (ref "U2") (pin "DRDY_M") (pinfunction "DRDY_M_DRDY_M") (pintype "bidirectional"))
    )
    (net (code "86") (name "unconnected-(U2-PadINT1_A{slash}G)") (class "Default")
      (node (ref "U2") (pin "INT1_A/G") (pinfunction "INT1_A/G_INT1_A/G") (pintype "bidirectional"))
    )
    (net (code "87") (name "unconnected-(U2-PadINT2_A{slash}G)") (class "Default")
      (node (ref "U2") (pin "INT2_A/G") (pinfunction "INT2_A/G_INT2_A/G") (pintype "bidirectional"))
    )
    (net (code "88") (name "unconnected-(U2-PadINT_M)") (class "Default")
      (node (ref "U2") (pin "INT_M") (pinfunction "INT_M_INT_M") (pintype "bidirectional"))
    )
  )
)
